# mechanical-endstop-shapeoko.net
KiCad netlist of a schematic drawn in EAGLE
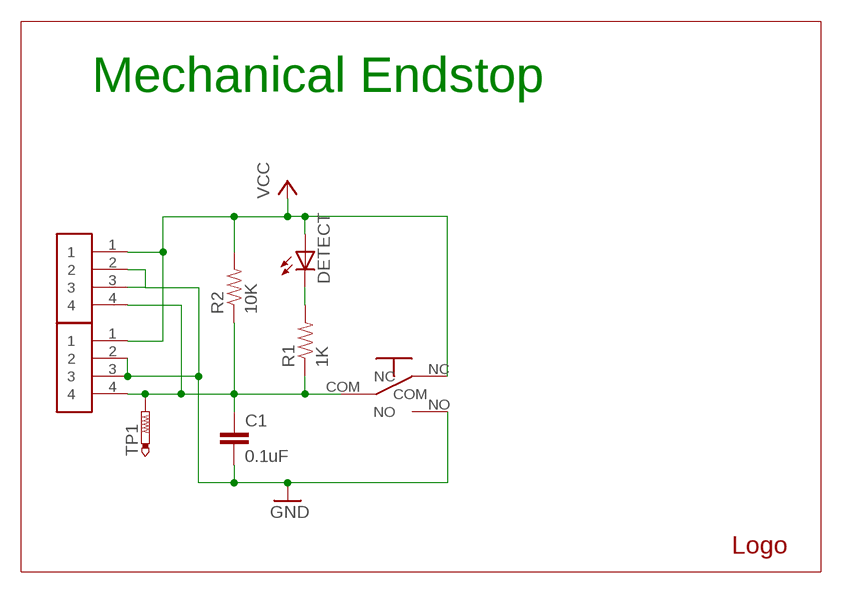
[diagram p0: schematic, sheet 1]

(export (version "E")
  (design (tool "Eeschema 10.0.6"))
  (components
    (comp (ref "C1")
      (value "0.1uF")
      (footprint "eagle-import:0805-CAP")
      (libsource (lib "eagle-import") (part "CAP-0805"))
    )
    (comp (ref "DETECT")
      (value "LED0603")
      (footprint "eagle-import:LED-0603")
      (libsource (lib "eagle-import") (part "LED0603"))
    )
    (comp (ref "R1")
      (value "1K")
      (footprint "eagle-import:R0805")
      (libsource (lib "eagle-import") (part "RESISTOR-0805"))
    )
    (comp (ref "R2")
      (value "10K")
      (footprint "eagle-import:R0805")
      (libsource (lib "eagle-import") (part "RESISTOR-0805"))
    )
    (comp (ref "TP1")
      (value "PTR1TP09R")
      (footprint "eagle-import:TP09R")
      (libsource (lib "eagle-import") (part "PTR1TP09R"))
    )
    (comp (ref "U$1")
      (value "CDROM-HOR")
      (footprint "eagle-import:70553-04")
      (libsource (lib "eagle-import") (part "CDROM-HOR"))
    )
    (comp (ref "U$2")
      (value "OMRON-D2FA")
      (footprint "eagle-import:OMRON-D2F-A")
      (libsource (lib "eagle-import") (part "OMRON-D2FA"))
    )
    (comp (ref "U$4")
      (value "OSHW-LOGO-OUTLINE")
      (footprint "eagle-import:OSHW-LOGO-OUTLINE")
      (libsource (lib "eagle-import") (part "OSHW-LOGO-OUTLINE"))
    )
    (comp (ref "U$5")
      (value "CDROM-HOR")
      (footprint "eagle-import:70553-04")
      (libsource (lib "eagle-import") (part "CDROM-HOR"))
    )
  )
  (nets
    (net (code "1") (name "GND") (class "Default")
      (node (ref "C1") (pin "2") (pinfunction "2_2") (pintype "passive"))
      (node (ref "U$1") (pin "2") (pinfunction "2_2") (pintype "bidirectional"))
      (node (ref "U$1") (pin "3") (pinfunction "3_3") (pintype "bidirectional"))
      (node (ref "U$2") (pin "NO") (pinfunction "NO_NO") (pintype "bidirectional"))
      (node (ref "U$5") (pin "2") (pinfunction "2_2") (pintype "bidirectional"))
      (node (ref "U$5") (pin "3") (pinfunction "3_3") (pintype "bidirectional"))
    )
    (net (code "2") (name "Net-(C1-Pad1)") (class "Default")
      (node (ref "C1") (pin "1") (pinfunction "1_1") (pintype "passive"))
      (node (ref "R1") (pin "1") (pinfunction "1_1") (pintype "passive"))
      (node (ref "R2") (pin "1") (pinfunction "1_1") (pintype "passive"))
      (node (ref "TP1") (pin "TP") (pinfunction "TP_TP") (pintype "input"))
      (node (ref "U$1") (pin "4") (pinfunction "4_4") (pintype "bidirectional"))
      (node (ref "U$2") (pin "COM") (pinfunction "COM_COM") (pintype "bidirectional"))
      (node (ref "U$5") (pin "4") (pinfunction "4_4") (pintype "bidirectional"))
    )
    (net (code "3") (name "Net-(DETECT-PadC)") (class "Default")
      (node (ref "DETECT") (pin "C") (pinfunction "C_C") (pintype "passive"))
      (node (ref "R1") (pin "2") (pinfunction "2_2") (pintype "passive"))
    )
    (net (code "4") (name "VCC") (class "Default")
      (node (ref "DETECT") (pin "A") (pinfunction "A_A") (pintype "passive"))
      (node (ref "R2") (pin "2") (pinfunction "2_2") (pintype "passive"))
      (node (ref "U$1") (pin "1") (pinfunction "1_1") (pintype "bidirectional"))
      (node (ref "U$2") (pin "NC") (pinfunction "NC_NC") (pintype "bidirectional"))
      (node (ref "U$5") (pin "1") (pinfunction "1_1") (pintype "bidirectional"))
    )
  )
)
